# Main.net
KiCad netlist of a schematic drawn in Altium Designer
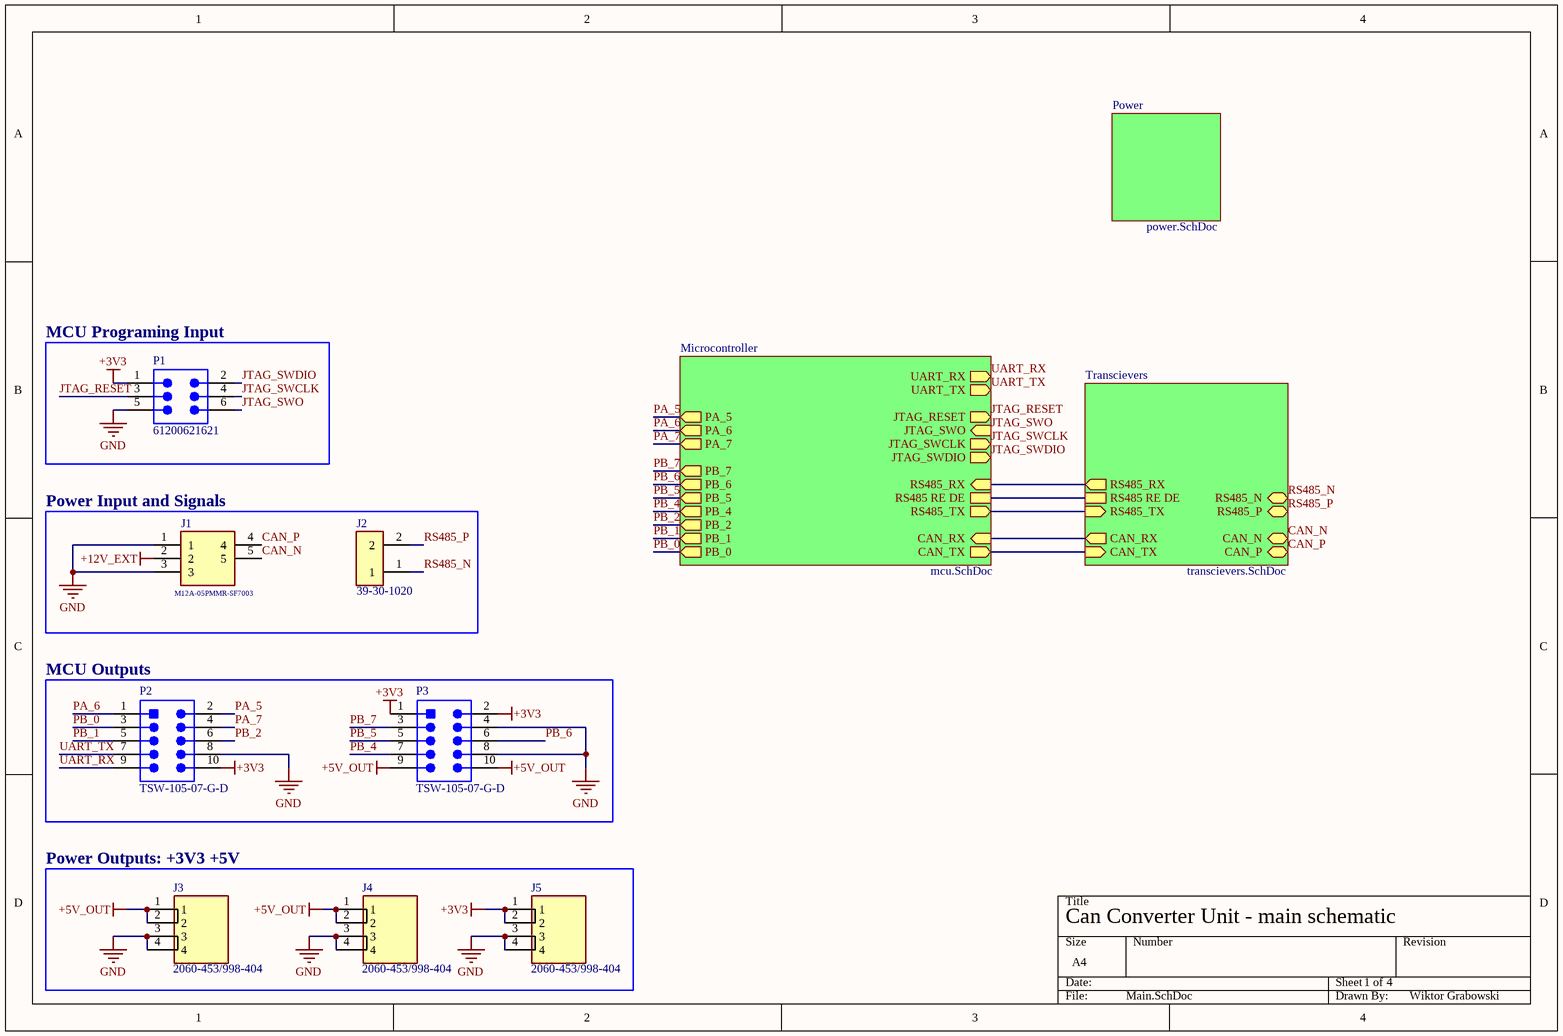
[diagram p0: Main.SchDoc]

(export (version "E")
  (design (tool "Eeschema 10.0.6"))
  (components
    (comp (ref "J1")
      (value "M12A-05PMMR-SF7003")
      (footprint "M12A05PMMRSF7003")
      (description "M12, A Code, 4A, 05 pins, Male Contact, Hexagonal, M12*1.0, PCB 90ø, Front Fastened, IP67")
      (fields
        (field (name "MOUSER PART NUMBER") "523-M12A05PMMRSF7003")
        (field (name "MANUFACTURER") "Amphenol LTW")
      )
      (libsource (lib "HydrogreenLibrary") (part "M12A-05PMMR-SF7003"))
    )
    (comp (ref "J2")
      (value "39-30-1020")
      (footprint "39-30-1020")
      (description "Pin Header, Power, 2 Rows, 2 Contacts, Through Hole Right Angle, Mini-Fit Jr. 5569")
      (fields (field (name "MANUFACTURER") "Molex"))
      (libsource (lib "HydrogreenLibrary") (part "39-30-1020"))
    )
    (comp (ref "J3")
      (value "2060-453/998-404")
      (footprint "WAGO-2060-452-998-404")
      (description "SMD Pcb Terminal Block, Push-button 0.75 MM² Pin Spacing 4 Mm 3-POLE White")
      (fields (field (name "MANUFACTURER") "WAGO"))
      (libsource (lib "HydrogreenLibrary") (part "WAGO-2060-452-998-404"))
    )
    (comp (ref "J4")
      (value "2060-453/998-404")
      (footprint "WAGO-2060-452-998-404")
      (description "SMD Pcb Terminal Block, Push-button 0.75 MM² Pin Spacing 4 Mm 3-POLE White")
      (fields (field (name "MANUFACTURER") "WAGO"))
      (libsource (lib "HydrogreenLibrary") (part "WAGO-2060-452-998-404"))
    )
    (comp (ref "J5")
      (value "2060-453/998-404")
      (footprint "WAGO-2060-452-998-404")
      (description "SMD Pcb Terminal Block, Push-button 0.75 MM² Pin Spacing 4 Mm 3-POLE White")
      (fields (field (name "MANUFACTURER") "WAGO"))
      (libsource (lib "HydrogreenLibrary") (part "WAGO-2060-452-998-404"))
    )
    (comp (ref "P1")
      (value "61200621621")
      (footprint "61200621621")
      (libsource (lib "Altium Content Vault") (part "Header_Male_2R_06P"))
    )
    (comp (ref "P2")
      (value "TSW-105-07-G-D")
      (footprint "SMTC-TSW-105-07-G-D_V")
      (fields (field (name "MANUFACTURER") "Samtec-Inc."))
      (libsource (lib "Altium Content Vault") (part "CN-2P-M-R10"))
    )
    (comp (ref "P3")
      (value "TSW-105-07-G-D")
      (footprint "SMTC-TSW-105-07-G-D_V")
      (fields (field (name "MANUFACTURER") "Samtec-Inc."))
      (libsource (lib "Altium Content Vault") (part "CN-2P-M-R10"))
    )
  )
  (nets
    (net (code "1") (name "+3V3") (class "Default")
      (node (ref "J5") (pin "1") (pinfunction "1_1") (pintype "passive"))
      (node (ref "J5") (pin "2") (pinfunction "2_2") (pintype "passive"))
      (node (ref "P1") (pin "1") (pinfunction "1_1") (pintype "passive"))
      (node (ref "P2") (pin "10") (pinfunction "10_10") (pintype "passive"))
      (node (ref "P3") (pin "1") (pinfunction "1_1") (pintype "passive"))
      (node (ref "P3") (pin "2") (pinfunction "2_2") (pintype "passive"))
    )
    (net (code "2") (name "+5V_OUT") (class "Default")
      (node (ref "J3") (pin "1") (pinfunction "1_1") (pintype "passive"))
      (node (ref "J3") (pin "2") (pinfunction "2_2") (pintype "passive"))
      (node (ref "J4") (pin "1") (pinfunction "1_1") (pintype "passive"))
      (node (ref "J4") (pin "2") (pinfunction "2_2") (pintype "passive"))
      (node (ref "P3") (pin "10") (pinfunction "10_10") (pintype "passive"))
      (node (ref "P3") (pin "9") (pinfunction "9_9") (pintype "passive"))
    )
    (net (code "3") (name "+12V_EXT") (class "Default")
      (node (ref "J1") (pin "2") (pinfunction "2_2") (pintype "passive"))
    )
    (net (code "4") (name "/CAN_N") (class "Default")
      (node (ref "J1") (pin "5") (pinfunction "5_5") (pintype "passive"))
    )
    (net (code "5") (name "/CAN_P") (class "Default")
      (node (ref "J1") (pin "4") (pinfunction "4_4") (pintype "passive"))
    )
    (net (code "8") (name "/JTAG_RESET") (class "Default")
      (node (ref "P1") (pin "3") (pinfunction "3_3") (pintype "passive"))
    )
    (net (code "9") (name "/JTAG_SWCLK") (class "Default")
      (node (ref "P1") (pin "4") (pinfunction "4_4") (pintype "passive"))
    )
    (net (code "10") (name "/JTAG_SWDIO") (class "Default")
      (node (ref "P1") (pin "2") (pinfunction "2_2") (pintype "passive"))
    )
    (net (code "11") (name "/JTAG_SWO") (class "Default")
      (node (ref "P1") (pin "6") (pinfunction "6_6") (pintype "passive"))
    )
    (net (code "12") (name "/PA_5") (class "Default")
      (node (ref "P2") (pin "2") (pinfunction "2_2") (pintype "passive"))
    )
    (net (code "13") (name "/PA_6") (class "Default")
      (node (ref "P2") (pin "1") (pinfunction "1_1") (pintype "passive"))
    )
    (net (code "14") (name "/PA_7") (class "Default")
      (node (ref "P2") (pin "4") (pinfunction "4_4") (pintype "passive"))
    )
    (net (code "15") (name "/PB_0") (class "Default")
      (node (ref "P2") (pin "3") (pinfunction "3_3") (pintype "passive"))
    )
    (net (code "16") (name "/PB_1") (class "Default")
      (node (ref "P2") (pin "5") (pinfunction "5_5") (pintype "passive"))
    )
    (net (code "17") (name "/PB_2") (class "Default")
      (node (ref "P2") (pin "6") (pinfunction "6_6") (pintype "passive"))
    )
    (net (code "18") (name "/PB_4") (class "Default")
      (node (ref "P3") (pin "7") (pinfunction "7_7") (pintype "passive"))
    )
    (net (code "19") (name "/PB_5") (class "Default")
      (node (ref "P3") (pin "5") (pinfunction "5_5") (pintype "passive"))
    )
    (net (code "20") (name "/PB_6") (class "Default")
      (node (ref "P3") (pin "6") (pinfunction "6_6") (pintype "passive"))
    )
    (net (code "21") (name "/PB_7") (class "Default")
      (node (ref "P3") (pin "3") (pinfunction "3_3") (pintype "passive"))
    )
    (net (code "23") (name "/RS485_N") (class "Default")
      (node (ref "J2") (pin "1") (pinfunction "1_1") (pintype "passive"))
    )
    (net (code "24") (name "/RS485_P") (class "Default")
      (node (ref "J2") (pin "2") (pinfunction "2_2") (pintype "passive"))
    )
    (net (code "27") (name "/UART_RX") (class "Default")
      (node (ref "P2") (pin "9") (pinfunction "9_9") (pintype "passive"))
    )
    (net (code "28") (name "/UART_TX") (class "Default")
      (node (ref "P2") (pin "7") (pinfunction "7_7") (pintype "passive"))
    )
    (net (code "29") (name "GND") (class "Default")
      (node (ref "J1") (pin "1") (pinfunction "1_1") (pintype "passive"))
      (node (ref "J1") (pin "3") (pinfunction "3_3") (pintype "passive"))
      (node (ref "J3") (pin "3") (pinfunction "3_3") (pintype "passive"))
      (node (ref "J3") (pin "4") (pinfunction "4_4") (pintype "passive"))
      (node (ref "J4") (pin "3") (pinfunction "3_3") (pintype "passive"))
      (node (ref "J4") (pin "4") (pinfunction "4_4") (pintype "passive"))
      (node (ref "J5") (pin "3") (pinfunction "3_3") (pintype "passive"))
      (node (ref "J5") (pin "4") (pinfunction "4_4") (pintype "passive"))
      (node (ref "P1") (pin "5") (pinfunction "5_5") (pintype "passive"))
      (node (ref "P2") (pin "8") (pinfunction "8_8") (pintype "passive"))
      (node (ref "P3") (pin "4") (pinfunction "4_4") (pintype "passive"))
      (node (ref "P3") (pin "8") (pinfunction "8_8") (pintype "passive"))
    )
  )
)
